# Sheet1.net
KiCad netlist of a schematic drawn in Altium Designer
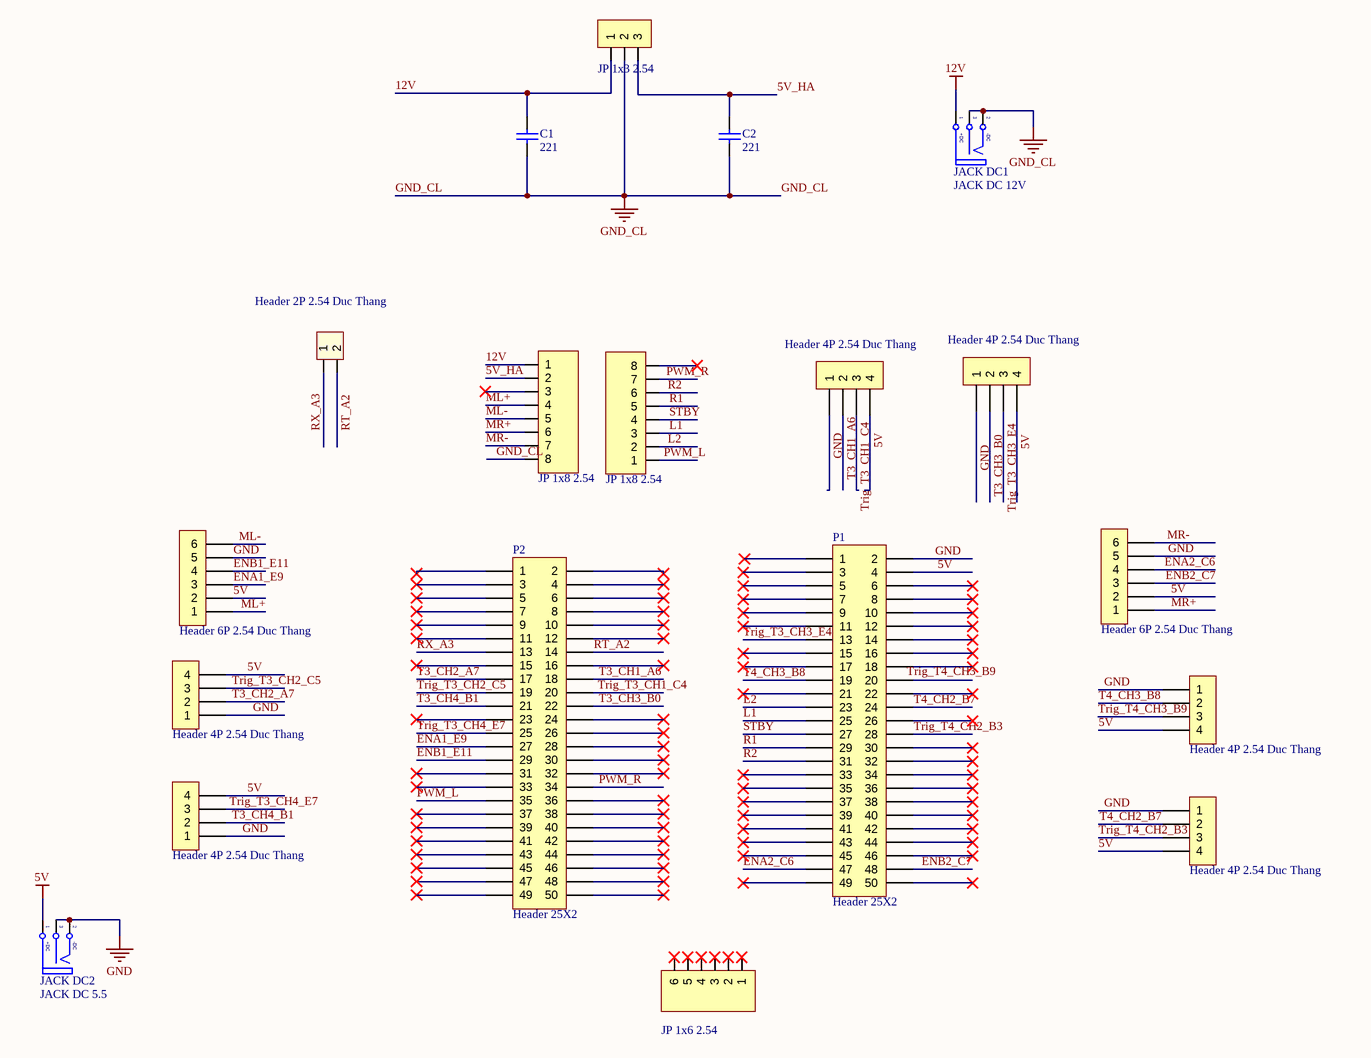
[diagram p0: Sheet1.SchDoc]

(export (version "E")
  (design (tool "Eeschema 10.0.6"))
  (components
    (comp (ref "C1")
      (value "221")
      (footprint "tu gom")
      (description "Cắm")
      (libsource (lib "Altium_Lib_by_KhueNguyenCreator") (part "Tu gom 221 50V"))
    )
    (comp (ref "C2")
      (value "221")
      (footprint "tu gom")
      (description "Cắm")
      (libsource (lib "Altium_Lib_by_KhueNguyenCreator") (part "Tu gom 221 50V"))
    )
    (comp (ref "H1")
      (value "Header 2P 2.54 Duc Thang")
      (footprint "XH2.54M-2")
      (description "Cắm")
      (libsource (lib "Altium_Lib_by_KhueNguyenCreator") (part "Header 2P 2.54 Duc Thang"))
    )
    (comp (ref "H2")
      (value "Header 4P 2.54 Duc Thang")
      (footprint "XH2.54M-4")
      (description "Cắm")
      (libsource (lib "") (part "Header 4P 2.54 Duc Thang_1"))
    )
    (comp (ref "H3")
      (value "Header 4P 2.54 Duc Thang")
      (footprint "XH2.54M-4")
      (description "Cắm")
      (libsource (lib "") (part "Header 4P 2.54 Duc Thang_1"))
    )
    (comp (ref "H4")
      (value "Header 6P 2.54 Duc Thang")
      (footprint "XH2.54M-6")
      (description "Cắm")
      (libsource (lib "Altium_Lib_by_KhueNguyenCreator") (part "Header 6P 2.54 Duc Thang"))
    )
    (comp (ref "H5")
      (value "Header 6P 2.54 Duc Thang")
      (footprint "XH2.54M-6")
      (description "Cắm")
      (libsource (lib "Altium_Lib_by_KhueNguyenCreator") (part "Header 6P 2.54 Duc Thang"))
    )
    (comp (ref "H6")
      (value "Header 4P 2.54 Duc Thang")
      (footprint "XH2.54M-4")
      (description "Cắm")
      (libsource (lib "Altium_Lib_by_KhueNguyenCreator") (part "Header 4P 2.54 Duc Thang"))
    )
    (comp (ref "H7")
      (value "Header 4P 2.54 Duc Thang")
      (footprint "XH2.54M-4")
      (description "Cắm")
      (libsource (lib "") (part "Header 4P 2.54 Duc Thang_2"))
    )
    (comp (ref "H8")
      (value "Header 4P 2.54 Duc Thang")
      (footprint "XH2.54M-4")
      (description "Cắm")
      (libsource (lib "Altium_Lib_by_KhueNguyenCreator") (part "Header 4P 2.54 Duc Thang"))
    )
    (comp (ref "H9")
      (value "Header 4P 2.54 Duc Thang")
      (footprint "XH2.54M-4")
      (description "Cắm")
      (libsource (lib "") (part "Header 4P 2.54 Duc Thang_2"))
    )
    (comp (ref "JACK DC1")
      (value "JACK DC 12V")
      (footprint "JACK DC 5.5")
      (description "JACK DC 5.5")
      (libsource (lib "Altium_Lib_by_KhueNguyenCreator") (part "JACK DC 5.5"))
    )
    (comp (ref "JACK DC2")
      (value "JACK DC 5.5")
      (footprint "JACK DC 5.5")
      (libsource (lib "Altium_Lib_by_KhueNguyenCreator") (part "JACK DC 5.5"))
    )
    (comp (ref "JP1")
      (value "JP 1x3 2.54")
      (footprint "JP 1x3 CT")
      (description "Cắm")
      (libsource (lib "Altium_Lib_by_KhueNguyenCreator") (part "JP 1x3 2.54 Cai Thang"))
    )
    (comp (ref "JP2")
      (value "JP 1x8 2.54")
      (footprint "JP 1x8 CT")
      (description "Cắm")
      (libsource (lib "") (part "JP 1x8 2.54 Cai Thang_1"))
    )
    (comp (ref "JP3")
      (value "JP 1x8 2.54")
      (footprint "JP 1x8 CT")
      (description "Cắm")
      (libsource (lib "Altium_Lib_by_KhueNguyenCreator") (part "JP 1x8 2.54 Cai Thang"))
    )
    (comp (ref "JP4")
      (value "JP 1x6 2.54")
      (footprint "JP 1x6 CT")
      (description "Cắm")
      (libsource (lib "Altium_Lib_by_KhueNguyenCreator") (part "JP 1x6 2.54 Cai Thang"))
    )
    (comp (ref "P1")
      (value "Header 25X2")
      (footprint "HDR2X25")
      (description "Header, 25-Pin, Dual row")
      (fields (field (name "PUBLISHER") "Altium Limited"))
      (libsource (lib "Schematic") (part "Header 25X2"))
    )
    (comp (ref "P2")
      (value "Header 25X2")
      (footprint "HDR2X25")
      (description "Header, 25-Pin, Dual row")
      (fields (field (name "PUBLISHER") "Altium Limited"))
      (libsource (lib "Schematic") (part "Header 25X2"))
    )
  )
  (nets
    (net (code "1") (name "/5V_HA") (class "Default")
      (node (ref "C2") (pin "1") (pinfunction "1_1") (pintype "passive"))
      (node (ref "JP1") (pin "3") (pinfunction "3_3") (pintype "passive"))
      (node (ref "JP2") (pin "2") (pinfunction "2_2") (pintype "passive"))
    )
    (net (code "2") (name "/ENA1_E9") (class "Default")
      (node (ref "H4") (pin "3") (pinfunction "3_3") (pintype "passive"))
      (node (ref "P2") (pin "27") (pinfunction "27_27") (pintype "passive"))
    )
    (net (code "3") (name "/ENA2_C6") (class "Default")
      (node (ref "H5") (pin "4") (pinfunction "4_4") (pintype "passive"))
      (node (ref "P1") (pin "47") (pinfunction "47_47") (pintype "passive"))
    )
    (net (code "4") (name "/ENB1_E11") (class "Default")
      (node (ref "H4") (pin "4") (pinfunction "4_4") (pintype "passive"))
      (node (ref "P2") (pin "29") (pinfunction "29_29") (pintype "passive"))
    )
    (net (code "5") (name "/ENB2_C7") (class "Default")
      (node (ref "H5") (pin "3") (pinfunction "3_3") (pintype "passive"))
      (node (ref "P1") (pin "48") (pinfunction "48_48") (pintype "passive"))
    )
    (net (code "6") (name "/L1") (class "Default")
      (node (ref "JP3") (pin "3") (pinfunction "3_3") (pintype "passive"))
      (node (ref "P1") (pin "25") (pinfunction "25_25") (pintype "passive"))
    )
    (net (code "7") (name "/L2") (class "Default")
      (node (ref "JP3") (pin "2") (pinfunction "2_2") (pintype "passive"))
      (node (ref "P1") (pin "23") (pinfunction "23_23") (pintype "passive"))
    )
    (net (code "8") (name "/ML+") (class "Default")
      (node (ref "H4") (pin "1") (pinfunction "1_1") (pintype "passive"))
      (node (ref "JP2") (pin "4") (pinfunction "4_4") (pintype "passive"))
    )
    (net (code "9") (name "/ML-") (class "Default")
      (node (ref "H4") (pin "6") (pinfunction "6_6") (pintype "passive"))
      (node (ref "JP2") (pin "5") (pinfunction "5_5") (pintype "passive"))
    )
    (net (code "10") (name "/MR+") (class "Default")
      (node (ref "H5") (pin "1") (pinfunction "1_1") (pintype "passive"))
      (node (ref "JP2") (pin "6") (pinfunction "6_6") (pintype "passive"))
    )
    (net (code "11") (name "/MR-") (class "Default")
      (node (ref "H5") (pin "6") (pinfunction "6_6") (pintype "passive"))
      (node (ref "JP2") (pin "7") (pinfunction "7_7") (pintype "passive"))
    )
    (net (code "12") (name "/PWM_L") (class "Default")
      (node (ref "JP3") (pin "1") (pinfunction "1_1") (pintype "passive"))
      (node (ref "P2") (pin "35") (pinfunction "35_35") (pintype "passive"))
    )
    (net (code "13") (name "/PWM_R") (class "Default")
      (node (ref "JP3") (pin "7") (pinfunction "7_7") (pintype "passive"))
      (node (ref "P2") (pin "34") (pinfunction "34_34") (pintype "passive"))
    )
    (net (code "14") (name "/R1") (class "Default")
      (node (ref "JP3") (pin "5") (pinfunction "5_5") (pintype "passive"))
      (node (ref "P1") (pin "29") (pinfunction "29_29") (pintype "passive"))
    )
    (net (code "15") (name "/R2") (class "Default")
      (node (ref "JP3") (pin "6") (pinfunction "6_6") (pintype "passive"))
      (node (ref "P1") (pin "31") (pinfunction "31_31") (pintype "passive"))
    )
    (net (code "16") (name "/RT_A2") (class "Default")
      (node (ref "H1") (pin "2") (pinfunction "2_2") (pintype "passive"))
      (node (ref "P2") (pin "14") (pinfunction "14_14") (pintype "passive"))
    )
    (net (code "17") (name "/RX_A3") (class "Default")
      (node (ref "H1") (pin "1") (pinfunction "1_1") (pintype "passive"))
      (node (ref "P2") (pin "13") (pinfunction "13_13") (pintype "passive"))
    )
    (net (code "18") (name "/STBY") (class "Default")
      (node (ref "JP3") (pin "4") (pinfunction "4_4") (pintype "passive"))
      (node (ref "P1") (pin "27") (pinfunction "27_27") (pintype "passive"))
    )
    (net (code "19") (name "/T3_CH1_A6") (class "Default")
      (node (ref "H3") (pin "2") (pinfunction "2_2") (pintype "passive"))
      (node (ref "P2") (pin "18") (pinfunction "18_18") (pintype "passive"))
    )
    (net (code "20") (name "/T3_CH2_A7") (class "Default")
      (node (ref "H6") (pin "2") (pinfunction "2_2") (pintype "passive"))
      (node (ref "P2") (pin "17") (pinfunction "17_17") (pintype "passive"))
    )
    (net (code "21") (name "/T3_CH3_B0") (class "Default")
      (node (ref "H2") (pin "2") (pinfunction "2_2") (pintype "passive"))
      (node (ref "P2") (pin "22") (pinfunction "22_22") (pintype "passive"))
    )
    (net (code "22") (name "/T3_CH4_B1") (class "Default")
      (node (ref "H8") (pin "2") (pinfunction "2_2") (pintype "passive"))
      (node (ref "P2") (pin "21") (pinfunction "21_21") (pintype "passive"))
    )
    (net (code "23") (name "/T4_CH2_B7") (class "Default")
      (node (ref "H9") (pin "2") (pinfunction "2_2") (pintype "passive"))
      (node (ref "P1") (pin "24") (pinfunction "24_24") (pintype "passive"))
    )
    (net (code "24") (name "/T4_CH3_B8") (class "Default")
      (node (ref "H7") (pin "2") (pinfunction "2_2") (pintype "passive"))
      (node (ref "P1") (pin "19") (pinfunction "19_19") (pintype "passive"))
    )
    (net (code "25") (name "/Trig_T3_CH1_C4") (class "Default")
      (node (ref "H3") (pin "3") (pinfunction "3_3") (pintype "passive"))
      (node (ref "P2") (pin "20") (pinfunction "20_20") (pintype "passive"))
    )
    (net (code "26") (name "/Trig_T3_CH2_C5") (class "Default")
      (node (ref "H6") (pin "3") (pinfunction "3_3") (pintype "passive"))
      (node (ref "P2") (pin "19") (pinfunction "19_19") (pintype "passive"))
    )
    (net (code "27") (name "/Trig_T3_CH3_E4") (class "Default")
      (node (ref "H2") (pin "3") (pinfunction "3_3") (pintype "passive"))
      (node (ref "P1") (pin "13") (pinfunction "13_13") (pintype "passive"))
    )
    (net (code "28") (name "/Trig_T3_CH4_E7") (class "Default")
      (node (ref "H8") (pin "3") (pinfunction "3_3") (pintype "passive"))
      (node (ref "P2") (pin "25") (pinfunction "25_25") (pintype "passive"))
    )
    (net (code "29") (name "/Trig_T4_CH2_B3") (class "Default")
      (node (ref "H9") (pin "3") (pinfunction "3_3") (pintype "passive"))
      (node (ref "P1") (pin "28") (pinfunction "28_28") (pintype "passive"))
    )
    (net (code "30") (name "/Trig_T4_CH3_B9") (class "Default")
      (node (ref "H7") (pin "3") (pinfunction "3_3") (pintype "passive"))
    )
    (net (code "31") (name "5V") (class "Default")
      (node (ref "H2") (pin "4") (pinfunction "4_4") (pintype "passive"))
      (node (ref "H3") (pin "4") (pinfunction "4_4") (pintype "passive"))
      (node (ref "H4") (pin "2") (pinfunction "2_2") (pintype "passive"))
      (node (ref "H5") (pin "2") (pinfunction "2_2") (pintype "passive"))
      (node (ref "H6") (pin "4") (pinfunction "4_4") (pintype "passive"))
      (node (ref "H7") (pin "4") (pinfunction "4_4") (pintype "passive"))
      (node (ref "H8") (pin "4") (pinfunction "4_4") (pintype "passive"))
      (node (ref "H9") (pin "4") (pinfunction "4_4") (pintype "passive"))
      (node (ref "JACK DC2") (pin "1") (pinfunction "T_1") (pintype "passive"))
      (node (ref "P1") (pin "4") (pinfunction "4_4") (pintype "passive"))
    )
    (net (code "32") (name "12V") (class "Default")
      (node (ref "C1") (pin "1") (pinfunction "1_1") (pintype "passive"))
      (node (ref "JACK DC1") (pin "1") (pinfunction "T_1") (pintype "passive"))
      (node (ref "JP1") (pin "1") (pinfunction "1_1") (pintype "passive"))
      (node (ref "JP2") (pin "1") (pinfunction "1_1") (pintype "passive"))
    )
    (net (code "33") (name "GND") (class "Default")
      (node (ref "H2") (pin "1") (pinfunction "1_1") (pintype "passive"))
      (node (ref "H3") (pin "1") (pinfunction "1_1") (pintype "passive"))
      (node (ref "H4") (pin "5") (pinfunction "5_5") (pintype "passive"))
      (node (ref "H5") (pin "5") (pinfunction "5_5") (pintype "passive"))
      (node (ref "H6") (pin "1") (pinfunction "1_1") (pintype "passive"))
      (node (ref "H7") (pin "1") (pinfunction "1_1") (pintype "passive"))
      (node (ref "H8") (pin "1") (pinfunction "1_1") (pintype "passive"))
      (node (ref "H9") (pin "1") (pinfunction "1_1") (pintype "passive"))
      (node (ref "JACK DC2") (pin "2") (pinfunction "TN_2") (pintype "passive"))
      (node (ref "JACK DC2") (pin "3") (pinfunction "S_3") (pintype "power_in"))
      (node (ref "P1") (pin "2") (pinfunction "2_2") (pintype "passive"))
    )
    (net (code "34") (name "GND_CL") (class "Default")
      (node (ref "C1") (pin "2") (pinfunction "2_2") (pintype "passive"))
      (node (ref "C2") (pin "2") (pinfunction "2_2") (pintype "passive"))
      (node (ref "JACK DC1") (pin "2") (pinfunction "TN_2") (pintype "passive"))
      (node (ref "JACK DC1") (pin "3") (pinfunction "S_3") (pintype "power_in"))
      (node (ref "JP1") (pin "2") (pinfunction "2_2") (pintype "passive"))
      (node (ref "JP2") (pin "8") (pinfunction "8_8") (pintype "passive"))
    )
    (net (code "35") (name "unconnected-(JP2-Pad3)") (class "Default")
      (node (ref "JP2") (pin "3") (pinfunction "3_3") (pintype "passive+no_connect"))
    )
    (net (code "36") (name "unconnected-(JP3-Pad8)") (class "Default")
      (node (ref "JP3") (pin "8") (pinfunction "8_8") (pintype "passive+no_connect"))
    )
    (net (code "37") (name "unconnected-(JP4-Pad1)") (class "Default")
      (node (ref "JP4") (pin "1") (pinfunction "1_1") (pintype "passive+no_connect"))
    )
    (net (code "38") (name "unconnected-(JP4-Pad2)") (class "Default")
      (node (ref "JP4") (pin "2") (pinfunction "2_2") (pintype "passive+no_connect"))
    )
    (net (code "39") (name "unconnected-(JP4-Pad3)") (class "Default")
      (node (ref "JP4") (pin "3") (pinfunction "3_3") (pintype "passive+no_connect"))
    )
    (net (code "40") (name "unconnected-(JP4-Pad4)") (class "Default")
      (node (ref "JP4") (pin "4") (pinfunction "4_4") (pintype "passive+no_connect"))
    )
    (net (code "41") (name "unconnected-(JP4-Pad5)") (class "Default")
      (node (ref "JP4") (pin "5") (pinfunction "5_5") (pintype "passive+no_connect"))
    )
    (net (code "42") (name "unconnected-(JP4-Pad6)") (class "Default")
      (node (ref "JP4") (pin "6") (pinfunction "6_6") (pintype "passive+no_connect"))
    )
    (net (code "43") (name "unconnected-(P1-Pad1)") (class "Default")
      (node (ref "P1") (pin "1") (pinfunction "1_1") (pintype "passive+no_connect"))
    )
    (net (code "44") (name "unconnected-(P1-Pad3)") (class "Default")
      (node (ref "P1") (pin "3") (pinfunction "3_3") (pintype "passive+no_connect"))
    )
    (net (code "45") (name "unconnected-(P1-Pad5)") (class "Default")
      (node (ref "P1") (pin "5") (pinfunction "5_5") (pintype "passive+no_connect"))
    )
    (net (code "46") (name "unconnected-(P1-Pad6)") (class "Default")
      (node (ref "P1") (pin "6") (pinfunction "6_6") (pintype "passive+no_connect"))
    )
    (net (code "47") (name "unconnected-(P1-Pad7)") (class "Default")
      (node (ref "P1") (pin "7") (pinfunction "7_7") (pintype "passive+no_connect"))
    )
    (net (code "48") (name "unconnected-(P1-Pad8)") (class "Default")
      (node (ref "P1") (pin "8") (pinfunction "8_8") (pintype "passive+no_connect"))
    )
    (net (code "49") (name "unconnected-(P1-Pad9)") (class "Default")
      (node (ref "P1") (pin "9") (pinfunction "9_9") (pintype "passive+no_connect"))
    )
    (net (code "50") (name "unconnected-(P1-Pad10)") (class "Default")
      (node (ref "P1") (pin "10") (pinfunction "10_10") (pintype "passive+no_connect"))
    )
    (net (code "51") (name "unconnected-(P1-Pad11)") (class "Default")
      (node (ref "P1") (pin "11") (pinfunction "11_11") (pintype "passive+no_connect"))
    )
    (net (code "52") (name "unconnected-(P1-Pad12)") (class "Default")
      (node (ref "P1") (pin "12") (pinfunction "12_12") (pintype "passive+no_connect"))
    )
    (net (code "53") (name "unconnected-(P1-Pad14)") (class "Default")
      (node (ref "P1") (pin "14") (pinfunction "14_14") (pintype "passive+no_connect"))
    )
    (net (code "54") (name "unconnected-(P1-Pad15)") (class "Default")
      (node (ref "P1") (pin "15") (pinfunction "15_15") (pintype "passive+no_connect"))
    )
    (net (code "55") (name "unconnected-(P1-Pad16)") (class "Default")
      (node (ref "P1") (pin "16") (pinfunction "16_16") (pintype "passive+no_connect"))
    )
    (net (code "56") (name "unconnected-(P1-Pad17)") (class "Default")
      (node (ref "P1") (pin "17") (pinfunction "17_17") (pintype "passive+no_connect"))
    )
    (net (code "57") (name "unconnected-(P1-Pad18)") (class "Default")
      (node (ref "P1") (pin "18") (pinfunction "18_18") (pintype "passive+no_connect"))
    )
    (net (code "58") (name "unconnected-(P1-Pad20)") (class "Default")
      (node (ref "P1") (pin "20") (pinfunction "20_20") (pintype "passive"))
    )
    (net (code "59") (name "unconnected-(P1-Pad21)") (class "Default")
      (node (ref "P1") (pin "21") (pinfunction "21_21") (pintype "passive+no_connect"))
    )
    (net (code "60") (name "unconnected-(P1-Pad22)") (class "Default")
      (node (ref "P1") (pin "22") (pinfunction "22_22") (pintype "passive+no_connect"))
    )
    (net (code "61") (name "unconnected-(P1-Pad26)") (class "Default")
      (node (ref "P1") (pin "26") (pinfunction "26_26") (pintype "passive+no_connect"))
    )
    (net (code "62") (name "unconnected-(P1-Pad30)") (class "Default")
      (node (ref "P1") (pin "30") (pinfunction "30_30") (pintype "passive+no_connect"))
    )
    (net (code "63") (name "unconnected-(P1-Pad32)") (class "Default")
      (node (ref "P1") (pin "32") (pinfunction "32_32") (pintype "passive+no_connect"))
    )
    (net (code "64") (name "unconnected-(P1-Pad33)") (class "Default")
      (node (ref "P1") (pin "33") (pinfunction "33_33") (pintype "passive+no_connect"))
    )
    (net (code "65") (name "unconnected-(P1-Pad34)") (class "Default")
      (node (ref "P1") (pin "34") (pinfunction "34_34") (pintype "passive+no_connect"))
    )
    (net (code "66") (name "unconnected-(P1-Pad35)") (class "Default")
      (node (ref "P1") (pin "35") (pinfunction "35_35") (pintype "passive+no_connect"))
    )
    (net (code "67") (name "unconnected-(P1-Pad36)") (class "Default")
      (node (ref "P1") (pin "36") (pinfunction "36_36") (pintype "passive+no_connect"))
    )
    (net (code "68") (name "unconnected-(P1-Pad37)") (class "Default")
      (node (ref "P1") (pin "37") (pinfunction "37_37") (pintype "passive+no_connect"))
    )
    (net (code "69") (name "unconnected-(P1-Pad38)") (class "Default")
      (node (ref "P1") (pin "38") (pinfunction "38_38") (pintype "passive+no_connect"))
    )
    (net (code "70") (name "unconnected-(P1-Pad39)") (class "Default")
      (node (ref "P1") (pin "39") (pinfunction "39_39") (pintype "passive+no_connect"))
    )
    (net (code "71") (name "unconnected-(P1-Pad40)") (class "Default")
      (node (ref "P1") (pin "40") (pinfunction "40_40") (pintype "passive+no_connect"))
    )
    (net (code "72") (name "unconnected-(P1-Pad41)") (class "Default")
      (node (ref "P1") (pin "41") (pinfunction "41_41") (pintype "passive+no_connect"))
    )
    (net (code "73") (name "unconnected-(P1-Pad42)") (class "Default")
      (node (ref "P1") (pin "42") (pinfunction "42_42") (pintype "passive+no_connect"))
    )
    (net (code "74") (name "unconnected-(P1-Pad43)") (class "Default")
      (node (ref "P1") (pin "43") (pinfunction "43_43") (pintype "passive+no_connect"))
    )
    (net (code "75") (name "unconnected-(P1-Pad44)") (class "Default")
      (node (ref "P1") (pin "44") (pinfunction "44_44") (pintype "passive+no_connect"))
    )
    (net (code "76") (name "unconnected-(P1-Pad45)") (class "Default")
      (node (ref "P1") (pin "45") (pinfunction "45_45") (pintype "passive+no_connect"))
    )
    (net (code "77") (name "unconnected-(P1-Pad46)") (class "Default")
      (node (ref "P1") (pin "46") (pinfunction "46_46") (pintype "passive+no_connect"))
    )
    (net (code "78") (name "unconnected-(P1-Pad49)") (class "Default")
      (node (ref "P1") (pin "49") (pinfunction "49_49") (pintype "passive+no_connect"))
    )
    (net (code "79") (name "unconnected-(P1-Pad50)") (class "Default")
      (node (ref "P1") (pin "50") (pinfunction "50_50") (pintype "passive+no_connect"))
    )
    (net (code "80") (name "unconnected-(P2-Pad1)") (class "Default")
      (node (ref "P2") (pin "1") (pinfunction "1_1") (pintype "passive+no_connect"))
    )
    (net (code "81") (name "unconnected-(P2-Pad2)") (class "Default")
      (node (ref "P2") (pin "2") (pinfunction "2_2") (pintype "passive+no_connect"))
    )
    (net (code "82") (name "unconnected-(P2-Pad3)") (class "Default")
      (node (ref "P2") (pin "3") (pinfunction "3_3") (pintype "passive+no_connect"))
    )
    (net (code "83") (name "unconnected-(P2-Pad4)") (class "Default")
      (node (ref "P2") (pin "4") (pinfunction "4_4") (pintype "passive+no_connect"))
    )
    (net (code "84") (name "unconnected-(P2-Pad5)") (class "Default")
      (node (ref "P2") (pin "5") (pinfunction "5_5") (pintype "passive+no_connect"))
    )
    (net (code "85") (name "unconnected-(P2-Pad6)") (class "Default")
      (node (ref "P2") (pin "6") (pinfunction "6_6") (pintype "passive+no_connect"))
    )
    (net (code "86") (name "unconnected-(P2-Pad7)") (class "Default")
      (node (ref "P2") (pin "7") (pinfunction "7_7") (pintype "passive+no_connect"))
    )
    (net (code "87") (name "unconnected-(P2-Pad8)") (class "Default")
      (node (ref "P2") (pin "8") (pinfunction "8_8") (pintype "passive+no_connect"))
    )
    (net (code "88") (name "unconnected-(P2-Pad9)") (class "Default")
      (node (ref "P2") (pin "9") (pinfunction "9_9") (pintype "passive+no_connect"))
    )
    (net (code "89") (name "unconnected-(P2-Pad10)") (class "Default")
      (node (ref "P2") (pin "10") (pinfunction "10_10") (pintype "passive+no_connect"))
    )
    (net (code "90") (name "unconnected-(P2-Pad11)") (class "Default")
      (node (ref "P2") (pin "11") (pinfunction "11_11") (pintype "passive+no_connect"))
    )
    (net (code "91") (name "unconnected-(P2-Pad12)") (class "Default")
      (node (ref "P2") (pin "12") (pinfunction "12_12") (pintype "passive+no_connect"))
    )
    (net (code "92") (name "unconnected-(P2-Pad15)") (class "Default")
      (node (ref "P2") (pin "15") (pinfunction "15_15") (pintype "passive+no_connect"))
    )
    (net (code "93") (name "unconnected-(P2-Pad16)") (class "Default")
      (node (ref "P2") (pin "16") (pinfunction "16_16") (pintype "passive+no_connect"))
    )
    (net (code "94") (name "unconnected-(P2-Pad23)") (class "Default")
      (node (ref "P2") (pin "23") (pinfunction "23_23") (pintype "passive+no_connect"))
    )
    (net (code "95") (name "unconnected-(P2-Pad24)") (class "Default")
      (node (ref "P2") (pin "24") (pinfunction "24_24") (pintype "passive+no_connect"))
    )
    (net (code "96") (name "unconnected-(P2-Pad26)") (class "Default")
      (node (ref "P2") (pin "26") (pinfunction "26_26") (pintype "passive+no_connect"))
    )
    (net (code "97") (name "unconnected-(P2-Pad28)") (class "Default")
      (node (ref "P2") (pin "28") (pinfunction "28_28") (pintype "passive+no_connect"))
    )
    (net (code "98") (name "unconnected-(P2-Pad30)") (class "Default")
      (node (ref "P2") (pin "30") (pinfunction "30_30") (pintype "passive+no_connect"))
    )
    (net (code "99") (name "unconnected-(P2-Pad31)") (class "Default")
      (node (ref "P2") (pin "31") (pinfunction "31_31") (pintype "passive+no_connect"))
    )
    (net (code "100") (name "unconnected-(P2-Pad32)") (class "Default")
      (node (ref "P2") (pin "32") (pinfunction "32_32") (pintype "passive+no_connect"))
    )
    (net (code "101") (name "unconnected-(P2-Pad33)") (class "Default")
      (node (ref "P2") (pin "33") (pinfunction "33_33") (pintype "passive+no_connect"))
    )
    (net (code "102") (name "unconnected-(P2-Pad36)") (class "Default")
      (node (ref "P2") (pin "36") (pinfunction "36_36") (pintype "passive+no_connect"))
    )
    (net (code "103") (name "unconnected-(P2-Pad37)") (class "Default")
      (node (ref "P2") (pin "37") (pinfunction "37_37") (pintype "passive+no_connect"))
    )
    (net (code "104") (name "unconnected-(P2-Pad38)") (class "Default")
      (node (ref "P2") (pin "38") (pinfunction "38_38") (pintype "passive+no_connect"))
    )
    (net (code "105") (name "unconnected-(P2-Pad39)") (class "Default")
      (node (ref "P2") (pin "39") (pinfunction "39_39") (pintype "passive+no_connect"))
    )
    (net (code "106") (name "unconnected-(P2-Pad40)") (class "Default")
      (node (ref "P2") (pin "40") (pinfunction "40_40") (pintype "passive+no_connect"))
    )
    (net (code "107") (name "unconnected-(P2-Pad41)") (class "Default")
      (node (ref "P2") (pin "41") (pinfunction "41_41") (pintype "passive+no_connect"))
    )
    (net (code "108") (name "unconnected-(P2-Pad42)") (class "Default")
      (node (ref "P2") (pin "42") (pinfunction "42_42") (pintype "passive+no_connect"))
    )
    (net (code "109") (name "unconnected-(P2-Pad43)") (class "Default")
      (node (ref "P2") (pin "43") (pinfunction "43_43") (pintype "passive+no_connect"))
    )
    (net (code "110") (name "unconnected-(P2-Pad44)") (class "Default")
      (node (ref "P2") (pin "44") (pinfunction "44_44") (pintype "passive+no_connect"))
    )
    (net (code "111") (name "unconnected-(P2-Pad45)") (class "Default")
      (node (ref "P2") (pin "45") (pinfunction "45_45") (pintype "passive+no_connect"))
    )
    (net (code "112") (name "unconnected-(P2-Pad46)") (class "Default")
      (node (ref "P2") (pin "46") (pinfunction "46_46") (pintype "passive+no_connect"))
    )
    (net (code "113") (name "unconnected-(P2-Pad47)") (class "Default")
      (node (ref "P2") (pin "47") (pinfunction "47_47") (pintype "passive+no_connect"))
    )
    (net (code "114") (name "unconnected-(P2-Pad48)") (class "Default")
      (node (ref "P2") (pin "48") (pinfunction "48_48") (pintype "passive+no_connect"))
    )
    (net (code "115") (name "unconnected-(P2-Pad49)") (class "Default")
      (node (ref "P2") (pin "49") (pinfunction "49_49") (pintype "passive+no_connect"))
    )
    (net (code "116") (name "unconnected-(P2-Pad50)") (class "Default")
      (node (ref "P2") (pin "50") (pinfunction "50_50") (pintype "passive+no_connect"))
    )
  )
)
